# untitled.net
KiCad netlist of a schematic drawn in EAGLE
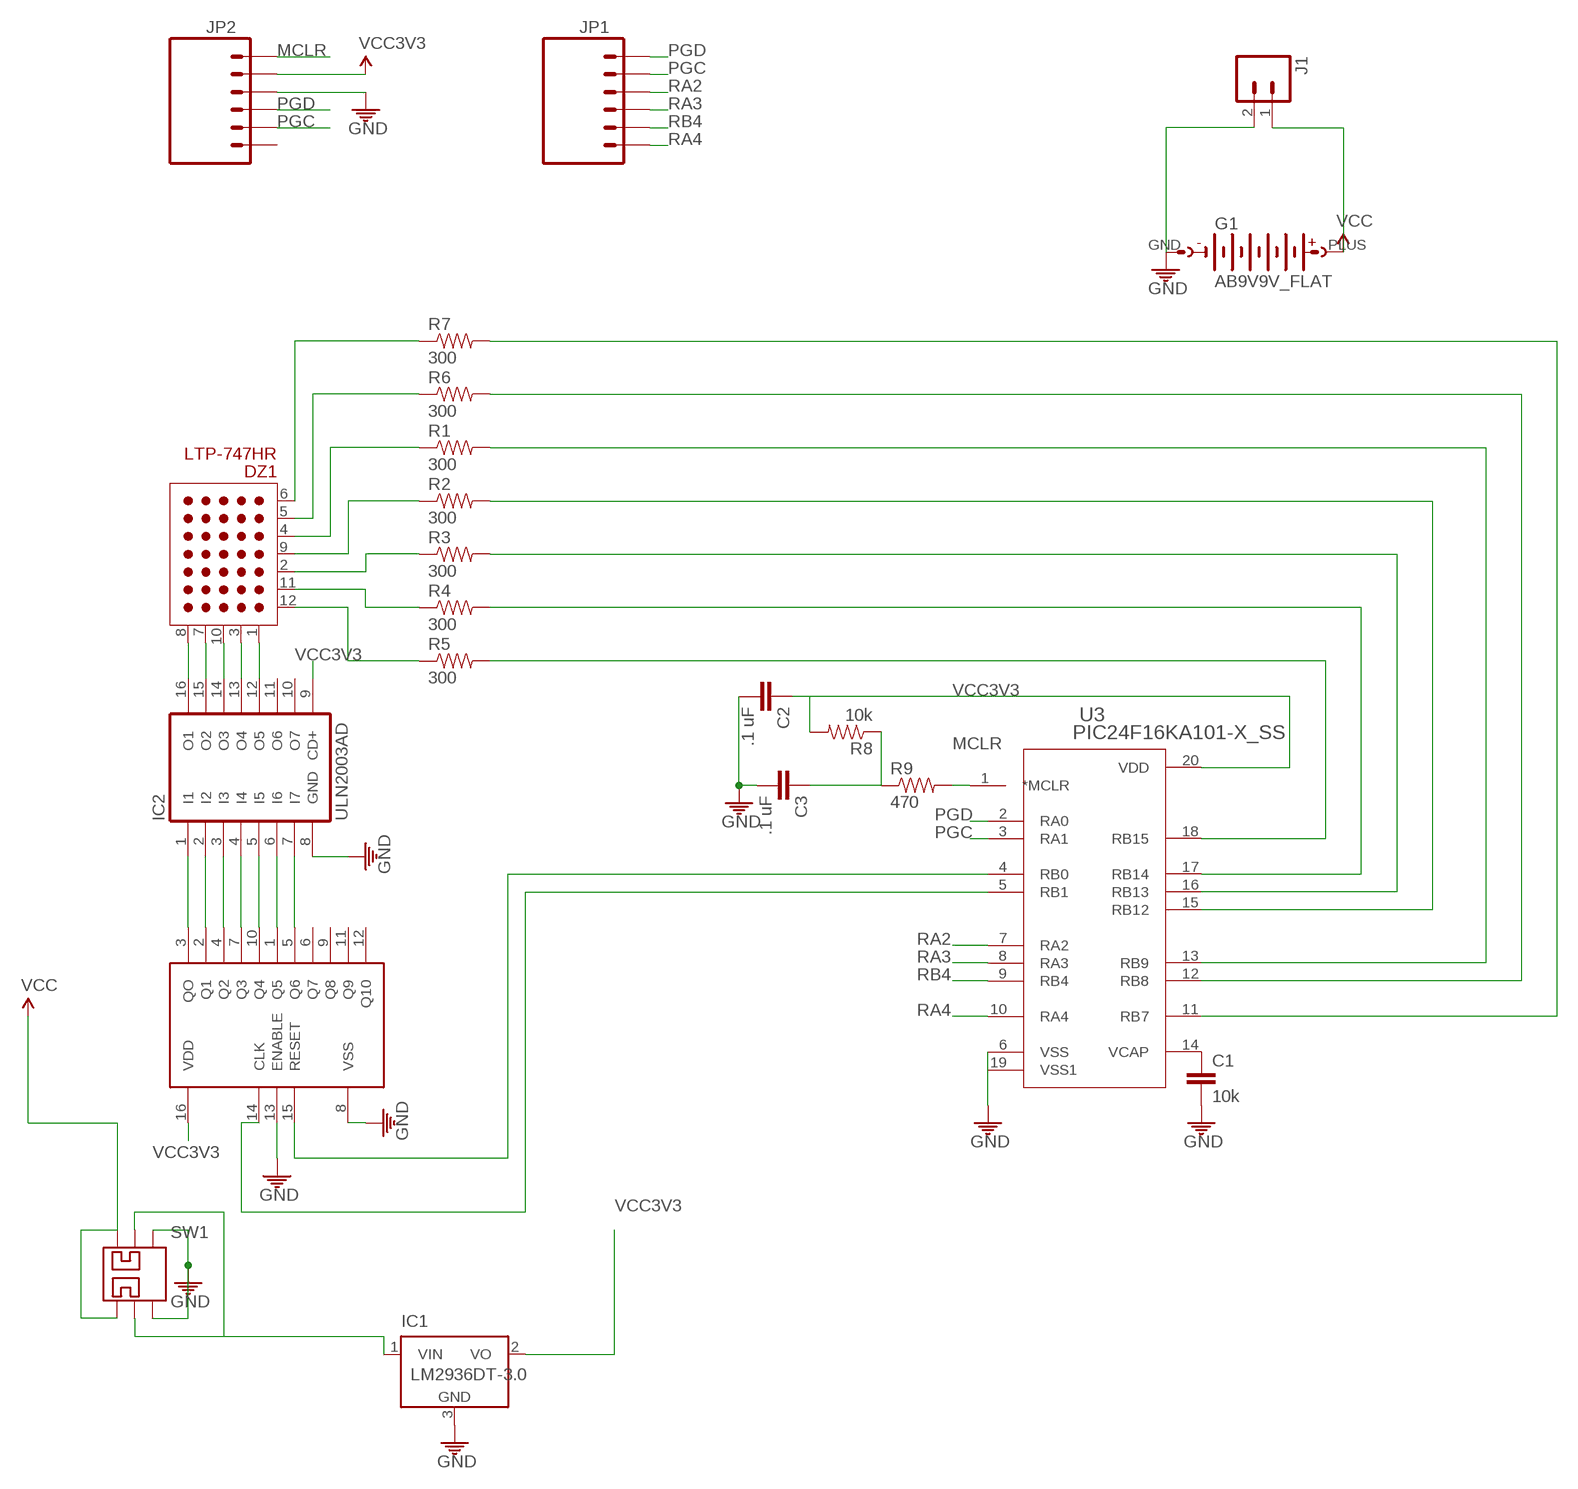
[diagram p0: schematic, sheet 1]

(export (version "E")
  (design (tool "Eeschema 10.0.6"))
  (components
    (comp (ref "C1")
      (value "10k")
      (footprint "eagle-import:1206")
      (libsource (lib "eagle-import") (part "CAP1206"))
    )
    (comp (ref "C2")
      (value ".1 uF")
      (footprint "eagle-import:1206")
      (libsource (lib "eagle-import") (part "CAP1206"))
    )
    (comp (ref "C3")
      (value ".1 uF")
      (footprint "eagle-import:1206")
      (libsource (lib "eagle-import") (part "CAP1206"))
    )
    (comp (ref "DZ1")
      (value "LTP-747HR")
      (footprint "eagle-import:LTP-747HR")
      (libsource (lib "eagle-import") (part "LTP-747HR"))
    )
    (comp (ref "G1")
      (value "AB9V9V_FLAT")
      (footprint "eagle-import:BH9VPC")
      (libsource (lib "eagle-import") (part "AB9V9V_FLAT"))
    )
    (comp (ref "IC1")
      (value "LM2936DT-3.0")
      (footprint "eagle-import:TO252")
      (fields (field (name "MF") "NATIONAL SEMICONDUCTOR"))
      (libsource (lib "eagle-import") (part "LM2936?DT-3.0"))
    )
    (comp (ref "IC2")
      (value "ULN2003AD")
      (footprint "eagle-import:SO16")
      (libsource (lib "eagle-import") (part "ULN2003AD"))
    )
    (comp (ref "J1")
      (value "M02PTH")
      (footprint "eagle-import:1X02")
      (libsource (lib "eagle-import") (part "M02PTH"))
    )
    (comp (ref "JP1")
      (value "M06LOCK")
      (footprint "eagle-import:1X06_LOCK")
      (libsource (lib "eagle-import") (part "M06LOCK"))
    )
    (comp (ref "JP2")
      (value "M06LOCK")
      (footprint "eagle-import:1X06_LOCK")
      (libsource (lib "eagle-import") (part "M06LOCK"))
    )
    (comp (ref "R1")
      (value "300")
      (footprint "eagle-import:0805")
      (libsource (lib "eagle-import") (part "RESISTOR0805-RES"))
    )
    (comp (ref "R2")
      (value "300")
      (footprint "eagle-import:0805")
      (libsource (lib "eagle-import") (part "RESISTOR0805-RES"))
    )
    (comp (ref "R3")
      (value "300")
      (footprint "eagle-import:0805")
      (libsource (lib "eagle-import") (part "RESISTOR0805-RES"))
    )
    (comp (ref "R4")
      (value "300")
      (footprint "eagle-import:0805")
      (libsource (lib "eagle-import") (part "RESISTOR0805-RES"))
    )
    (comp (ref "R5")
      (value "300")
      (footprint "eagle-import:0805")
      (libsource (lib "eagle-import") (part "RESISTOR0805-RES"))
    )
    (comp (ref "R6")
      (value "300")
      (footprint "eagle-import:0805")
      (libsource (lib "eagle-import") (part "RESISTOR0805-RES"))
    )
    (comp (ref "R7")
      (value "300")
      (footprint "eagle-import:0805")
      (libsource (lib "eagle-import") (part "RESISTOR0805-RES"))
    )
    (comp (ref "R8")
      (value "10k")
      (footprint "eagle-import:0805")
      (libsource (lib "eagle-import") (part "RESISTOR0805-RES"))
    )
    (comp (ref "R9")
      (value "470")
      (footprint "eagle-import:0805")
      (libsource (lib "eagle-import") (part "RESISTOR0805-RES"))
    )
    (comp (ref "SW1")
      (value "SLIDE_SWITCH_DPDTTOP")
      (footprint "eagle-import:EG2207")
      (libsource (lib "eagle-import") (part "SLIDE_SWITCH_DPDTTOP"))
    )
    (comp (ref "U1")
      (value "MC14017B")
      (footprint "eagle-import:SO16")
      (libsource (lib "eagle-import") (part "MC14017B"))
    )
    (comp (ref "U3")
      (value "PIC24F16KA101-X_SS")
      (footprint "eagle-import:SSOP20_MC")
      (libsource (lib "eagle-import") (part "PIC24F16KA101-X_SS"))
    )
  )
  (nets
    (net (code "1") (name "/MCLR") (class "Default")
      (node (ref "JP2") (pin "1") (pinfunction "1_1") (pintype "passive"))
      (node (ref "R9") (pin "2") (pinfunction "2_2") (pintype "passive"))
      (node (ref "U3") (pin "1") (pinfunction "*MCLR_1") (pintype "bidirectional"))
    )
    (net (code "2") (name "/PGC") (class "Default")
      (node (ref "JP1") (pin "2") (pinfunction "2_2") (pintype "passive"))
      (node (ref "JP2") (pin "5") (pinfunction "5_5") (pintype "passive"))
      (node (ref "U3") (pin "3") (pinfunction "RA1_3") (pintype "bidirectional"))
    )
    (net (code "3") (name "/PGD") (class "Default")
      (node (ref "JP1") (pin "1") (pinfunction "1_1") (pintype "passive"))
      (node (ref "JP2") (pin "4") (pinfunction "4_4") (pintype "passive"))
      (node (ref "U3") (pin "2") (pinfunction "RA0_2") (pintype "bidirectional"))
    )
    (net (code "4") (name "/RA2") (class "Default")
      (node (ref "JP1") (pin "3") (pinfunction "3_3") (pintype "passive"))
      (node (ref "U3") (pin "7") (pinfunction "RA2_7") (pintype "bidirectional"))
    )
    (net (code "5") (name "/RA3") (class "Default")
      (node (ref "JP1") (pin "4") (pinfunction "4_4") (pintype "passive"))
      (node (ref "U3") (pin "8") (pinfunction "RA3_8") (pintype "bidirectional"))
    )
    (net (code "6") (name "/RA4") (class "Default")
      (node (ref "JP1") (pin "6") (pinfunction "6_6") (pintype "passive"))
      (node (ref "U3") (pin "10") (pinfunction "RA4_10") (pintype "power_in"))
    )
    (net (code "7") (name "/RB4") (class "Default")
      (node (ref "JP1") (pin "5") (pinfunction "5_5") (pintype "passive"))
      (node (ref "U3") (pin "9") (pinfunction "RB4_9") (pintype "bidirectional"))
    )
    (net (code "8") (name "GND") (class "Default")
      (node (ref "C1") (pin "2") (pinfunction "2_2") (pintype "passive"))
      (node (ref "C2") (pin "2") (pinfunction "2_2") (pintype "passive"))
      (node (ref "C3") (pin "2") (pinfunction "2_2") (pintype "passive"))
      (node (ref "G1") (pin "GND") (pinfunction "-_GND") (pintype "passive"))
      (node (ref "IC1") (pin "3") (pinfunction "GND_3") (pintype "passive"))
      (node (ref "IC2") (pin "8") (pinfunction "GND_8") (pintype "power_in"))
      (node (ref "J1") (pin "2") (pinfunction "1_2") (pintype "passive"))
      (node (ref "JP2") (pin "3") (pinfunction "3_3") (pintype "passive"))
      (node (ref "SW1") (pin "P$3") (pinfunction "P$3_P$3") (pintype "bidirectional"))
      (node (ref "SW1") (pin "P$6") (pinfunction "P$6_P$6") (pintype "bidirectional"))
      (node (ref "U1") (pin "13") (pinfunction "ENABLE_13") (pintype "bidirectional"))
      (node (ref "U1") (pin "8") (pinfunction "VSS_8") (pintype "bidirectional"))
      (node (ref "U3") (pin "19") (pinfunction "VSS1_19") (pintype "bidirectional"))
      (node (ref "U3") (pin "6") (pinfunction "VSS_6") (pintype "bidirectional"))
    )
    (net (code "9") (name "Net-(C3-Pad1)") (class "Default")
      (node (ref "C3") (pin "1") (pinfunction "1_1") (pintype "passive"))
      (node (ref "R8") (pin "1") (pinfunction "1_1") (pintype "passive"))
      (node (ref "R9") (pin "1") (pinfunction "1_1") (pintype "passive"))
    )
    (net (code "10") (name "Net-(DZ1-C1)") (class "Default")
      (node (ref "DZ1") (pin "1") (pinfunction "C1_1") (pintype "passive"))
      (node (ref "IC2") (pin "12") (pinfunction "O5_12") (pintype "open_collector"))
    )
    (net (code "11") (name "Net-(DZ1-C2)") (class "Default")
      (node (ref "DZ1") (pin "3") (pinfunction "C2_3") (pintype "passive"))
      (node (ref "IC2") (pin "13") (pinfunction "O4_13") (pintype "open_collector"))
    )
    (net (code "12") (name "Net-(DZ1-C3)") (class "Default")
      (node (ref "DZ1") (pin "10") (pinfunction "C3_10") (pintype "passive"))
      (node (ref "IC2") (pin "14") (pinfunction "O3_14") (pintype "open_collector"))
    )
    (net (code "13") (name "Net-(DZ1-C4)") (class "Default")
      (node (ref "DZ1") (pin "7") (pinfunction "C4_7") (pintype "passive"))
      (node (ref "IC2") (pin "15") (pinfunction "O2_15") (pintype "open_collector"))
    )
    (net (code "14") (name "Net-(DZ1-C5)") (class "Default")
      (node (ref "DZ1") (pin "8") (pinfunction "C5_8") (pintype "passive"))
      (node (ref "IC2") (pin "16") (pinfunction "O1_16") (pintype "open_collector"))
    )
    (net (code "15") (name "Net-(DZ1-R1)") (class "Default")
      (node (ref "DZ1") (pin "12") (pinfunction "R1_12") (pintype "passive"))
      (node (ref "R5") (pin "1") (pinfunction "1_1") (pintype "passive"))
    )
    (net (code "16") (name "Net-(DZ1-R2)") (class "Default")
      (node (ref "DZ1") (pin "11") (pinfunction "R2_11") (pintype "passive"))
      (node (ref "R4") (pin "1") (pinfunction "1_1") (pintype "passive"))
    )
    (net (code "17") (name "Net-(DZ1-R3)") (class "Default")
      (node (ref "DZ1") (pin "2") (pinfunction "R3_2") (pintype "passive"))
      (node (ref "R3") (pin "1") (pinfunction "1_1") (pintype "passive"))
    )
    (net (code "18") (name "Net-(DZ1-R4)") (class "Default")
      (node (ref "DZ1") (pin "9") (pinfunction "R4_9") (pintype "passive"))
      (node (ref "R2") (pin "1") (pinfunction "1_1") (pintype "passive"))
    )
    (net (code "19") (name "Net-(DZ1-R5)") (class "Default")
      (node (ref "DZ1") (pin "4") (pinfunction "R5_4") (pintype "passive"))
      (node (ref "R1") (pin "1") (pinfunction "1_1") (pintype "passive"))
    )
    (net (code "20") (name "Net-(DZ1-R6)") (class "Default")
      (node (ref "DZ1") (pin "5") (pinfunction "R6_5") (pintype "passive"))
      (node (ref "R6") (pin "1") (pinfunction "1_1") (pintype "passive"))
    )
    (net (code "21") (name "Net-(DZ1-R7)") (class "Default")
      (node (ref "DZ1") (pin "6") (pinfunction "R7_6") (pintype "passive"))
      (node (ref "R7") (pin "1") (pinfunction "1_1") (pintype "passive"))
    )
    (net (code "22") (name "Net-(IC1-VIN)") (class "Default")
      (node (ref "IC1") (pin "1") (pinfunction "VIN_1") (pintype "input"))
      (node (ref "SW1") (pin "P$2") (pinfunction "P$2_P$2") (pintype "bidirectional"))
      (node (ref "SW1") (pin "P$5") (pinfunction "P$5_P$5") (pintype "bidirectional"))
    )
    (net (code "23") (name "Net-(IC2-I1)") (class "Default")
      (node (ref "IC2") (pin "1") (pinfunction "I1_1") (pintype "input"))
      (node (ref "U1") (pin "3") (pinfunction "QO_3") (pintype "bidirectional"))
    )
    (net (code "24") (name "Net-(IC2-I2)") (class "Default")
      (node (ref "IC2") (pin "2") (pinfunction "I2_2") (pintype "input"))
      (node (ref "U1") (pin "2") (pinfunction "Q1_2") (pintype "bidirectional"))
    )
    (net (code "25") (name "Net-(IC2-I3)") (class "Default")
      (node (ref "IC2") (pin "3") (pinfunction "I3_3") (pintype "input"))
      (node (ref "U1") (pin "4") (pinfunction "Q2_4") (pintype "bidirectional"))
    )
    (net (code "26") (name "Net-(IC2-I4)") (class "Default")
      (node (ref "IC2") (pin "4") (pinfunction "I4_4") (pintype "input"))
      (node (ref "U1") (pin "7") (pinfunction "Q3_7") (pintype "bidirectional"))
    )
    (net (code "27") (name "Net-(IC2-I5)") (class "Default")
      (node (ref "IC2") (pin "5") (pinfunction "I5_5") (pintype "input"))
      (node (ref "U1") (pin "10") (pinfunction "Q4_10") (pintype "bidirectional"))
    )
    (net (code "28") (name "Net-(IC2-I6)") (class "Default")
      (node (ref "IC2") (pin "6") (pinfunction "I6_6") (pintype "input"))
      (node (ref "U1") (pin "1") (pinfunction "Q5_1") (pintype "bidirectional"))
    )
    (net (code "29") (name "Net-(IC2-I7)") (class "Default")
      (node (ref "IC2") (pin "7") (pinfunction "I7_7") (pintype "input"))
      (node (ref "U1") (pin "5") (pinfunction "Q6_5") (pintype "bidirectional"))
    )
    (net (code "30") (name "Net-(U1-CLK)") (class "Default")
      (node (ref "U1") (pin "14") (pinfunction "CLK_14") (pintype "bidirectional"))
      (node (ref "U3") (pin "5") (pinfunction "RB1_5") (pintype "bidirectional"))
    )
    (net (code "31") (name "Net-(U1-RESET)") (class "Default")
      (node (ref "U1") (pin "15") (pinfunction "RESET_15") (pintype "bidirectional"))
      (node (ref "U3") (pin "4") (pinfunction "RB0_4") (pintype "bidirectional"))
    )
    (net (code "32") (name "Net-(U3-RB7)") (class "Default")
      (node (ref "R7") (pin "2") (pinfunction "2_2") (pintype "passive"))
      (node (ref "U3") (pin "11") (pinfunction "RB7_11") (pintype "power_in"))
    )
    (net (code "33") (name "Net-(U3-RB8)") (class "Default")
      (node (ref "R6") (pin "2") (pinfunction "2_2") (pintype "passive"))
      (node (ref "U3") (pin "12") (pinfunction "RB8_12") (pintype "bidirectional"))
    )
    (net (code "34") (name "Net-(U3-RB9)") (class "Default")
      (node (ref "R1") (pin "2") (pinfunction "2_2") (pintype "passive"))
      (node (ref "U3") (pin "13") (pinfunction "RB9_13") (pintype "bidirectional"))
    )
    (net (code "35") (name "Net-(U3-RB12)") (class "Default")
      (node (ref "R2") (pin "2") (pinfunction "2_2") (pintype "passive"))
      (node (ref "U3") (pin "15") (pinfunction "RB12_15") (pintype "bidirectional"))
    )
    (net (code "36") (name "Net-(U3-RB13)") (class "Default")
      (node (ref "R3") (pin "2") (pinfunction "2_2") (pintype "passive"))
      (node (ref "U3") (pin "16") (pinfunction "RB13_16") (pintype "bidirectional"))
    )
    (net (code "37") (name "Net-(U3-RB14)") (class "Default")
      (node (ref "R4") (pin "2") (pinfunction "2_2") (pintype "passive"))
      (node (ref "U3") (pin "17") (pinfunction "RB14_17") (pintype "bidirectional"))
    )
    (net (code "38") (name "Net-(U3-RB15)") (class "Default")
      (node (ref "R5") (pin "2") (pinfunction "2_2") (pintype "passive"))
      (node (ref "U3") (pin "18") (pinfunction "RB15_18") (pintype "bidirectional"))
    )
    (net (code "39") (name "Net-(U3-VCAP)") (class "Default")
      (node (ref "C1") (pin "1") (pinfunction "1_1") (pintype "passive"))
      (node (ref "U3") (pin "14") (pinfunction "VCAP_14") (pintype "bidirectional"))
    )
    (net (code "40") (name "VCC") (class "Default")
      (node (ref "G1") (pin "PLUS") (pinfunction "+_PLUS") (pintype "passive"))
      (node (ref "J1") (pin "1") (pinfunction "2_1") (pintype "passive"))
      (node (ref "SW1") (pin "P$1") (pinfunction "P$1_P$1") (pintype "bidirectional"))
      (node (ref "SW1") (pin "P$4") (pinfunction "P$4_P$4") (pintype "bidirectional"))
    )
    (net (code "41") (name "VCC3V3") (class "Default")
      (node (ref "C2") (pin "1") (pinfunction "1_1") (pintype "passive"))
      (node (ref "IC1") (pin "2") (pinfunction "VO_2") (pintype "passive"))
      (node (ref "IC2") (pin "9") (pinfunction "CD+_9") (pintype "passive"))
      (node (ref "JP2") (pin "2") (pinfunction "2_2") (pintype "passive"))
      (node (ref "R8") (pin "2") (pinfunction "2_2") (pintype "passive"))
      (node (ref "U1") (pin "16") (pinfunction "VDD_16") (pintype "bidirectional"))
      (node (ref "U3") (pin "20") (pinfunction "VDD_20") (pintype "bidirectional"))
    )
    (net (code "42") (name "unconnected-(IC2-O6-Pad11)") (class "Default")
      (node (ref "IC2") (pin "11") (pinfunction "O6_11") (pintype "open_collector"))
    )
    (net (code "43") (name "unconnected-(IC2-O7-Pad10)") (class "Default")
      (node (ref "IC2") (pin "10") (pinfunction "O7_10") (pintype "open_collector"))
    )
    (net (code "44") (name "unconnected-(JP2-Pad6)") (class "Default")
      (node (ref "JP2") (pin "6") (pinfunction "6_6") (pintype "passive"))
    )
    (net (code "45") (name "unconnected-(U1-Q7-Pad6)") (class "Default")
      (node (ref "U1") (pin "6") (pinfunction "Q7_6") (pintype "bidirectional"))
    )
    (net (code "46") (name "unconnected-(U1-Q8-Pad9)") (class "Default")
      (node (ref "U1") (pin "9") (pinfunction "Q8_9") (pintype "bidirectional"))
    )
    (net (code "47") (name "unconnected-(U1-Q9-Pad11)") (class "Default")
      (node (ref "U1") (pin "11") (pinfunction "Q9_11") (pintype "bidirectional"))
    )
    (net (code "48") (name "unconnected-(U1-Q10-Pad12)") (class "Default")
      (node (ref "U1") (pin "12") (pinfunction "Q10_12") (pintype "bidirectional"))
    )
  )
)
